# slit_lamp_goggles_PCB_compressed.net
KiCad netlist of a schematic drawn in Altium Designer
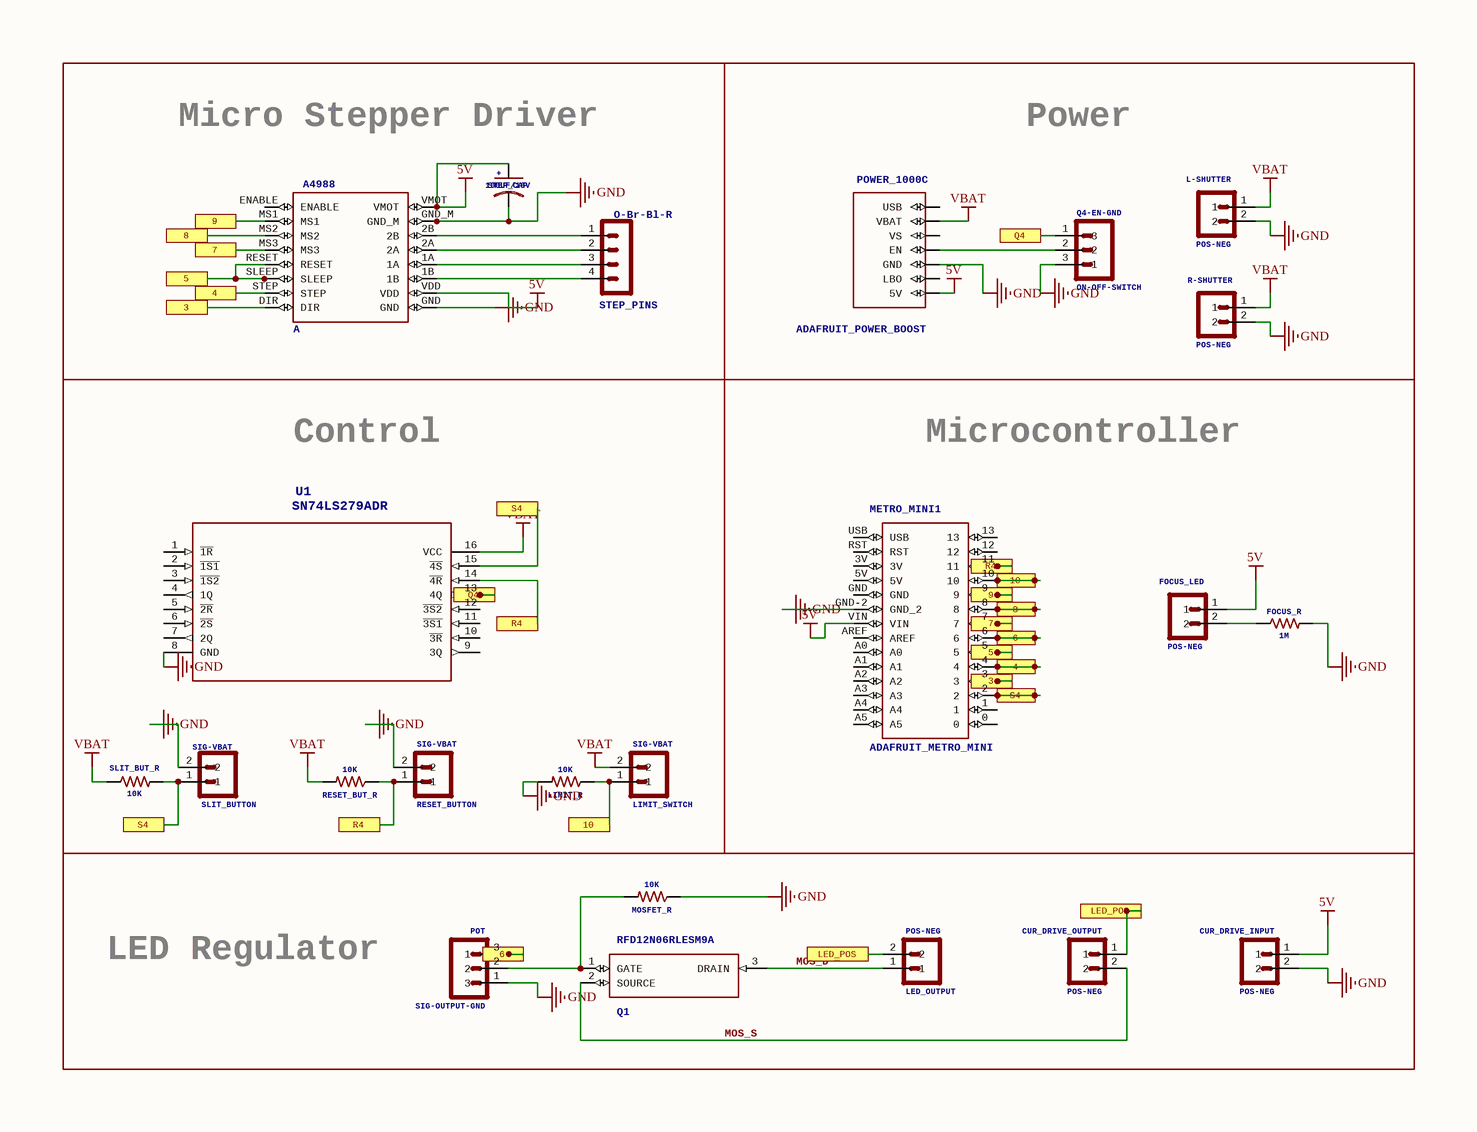
[diagram p0: slit_lamp_goggles_PCB_compressed.SchDoc]

(export (version "E")
  (design (tool "Eeschema 10.0.6"))
  (components
    (comp (ref "A4988")
      (value "A")
      (footprint "A4988")
      (description "Motor Drive for Stepper Motor")
      (libsource (lib "a4988_stepDriver") (part "A4988"))
    )
    (comp (ref "CUR_DRIVE_INPUT")
      (value "POS-NEG")
      (footprint "HDRVR2W64P254_1X2_558X254X850B")
      (description "2 Positions Header Connector 0.079\" (2.00mm) Through Hole Tin")
      (fields (field (name "MFR") "Sullins Connector Solutions") (field (name "MPN") "PPTC021LFBN-RC"))
      (libsource (lib "PiB_connectors") (part "1X02_PTH_VERT_FEMALE_2.54MM"))
    )
    (comp (ref "CUR_DRIVE_OUTPUT")
      (value "POS-NEG")
      (footprint "HDRVR2W64P254_1X2_558X254X850B")
      (description "2 Positions Header Connector 0.079\" (2.00mm) Through Hole Tin")
      (fields (field (name "MFR") "Sullins Connector Solutions") (field (name "MPN") "PPTC021LFBN-RC"))
      (libsource (lib "PiB_connectors") (part "1X02_PTH_VERT_FEMALE_2.54MM"))
    )
    (comp (ref "FOCUS_LED")
      (value "POS-NEG")
      (footprint "HDRVR2W64P254_1X2_558X254X850B")
      (description "2 Positions Header Connector 0.079\" (2.00mm) Through Hole Tin")
      (fields (field (name "MFR") "Sullins Connector Solutions") (field (name "MPN") "PPTC021LFBN-RC"))
      (libsource (lib "PiB_connectors") (part "1X02_PTH_VERT_FEMALE_2.54MM"))
    )
    (comp (ref "FOCUS_R")
      (value "1M")
      (footprint "RESISTOR-PTH-0207/7")
      (fields (field (name "CREATOR") "MrSwirlyEyes"))
      (libsource (lib "PiB_resistors") (part "RESISTOR_PTH-0207/7_1/8W-5%"))
    )
    (comp (ref "L-SHUTTER")
      (value "POS-NEG")
      (footprint "HDRVR2W64P254_1X2_558X254X850B")
      (description "2 Positions Header Connector 0.079\" (2.00mm) Through Hole Tin")
      (fields (field (name "MFR") "Sullins Connector Solutions") (field (name "MPN") "PPTC021LFBN-RC"))
      (libsource (lib "PiB_connectors") (part "1X02_PTH_VERT_FEMALE_2.54MM"))
    )
    (comp (ref "LED_OUTPUT")
      (value "POS-NEG")
      (footprint "HDRVR2W64P254_1X2_558X254X850B")
      (description "2 Positions Header Connector 0.079\" (2.00mm) Through Hole Tin")
      (fields (field (name "MFR") "Sullins Connector Solutions") (field (name "MPN") "PPTC021LFBN-RC"))
      (libsource (lib "PiB_connectors") (part "1X02_PTH_VERT_FEMALE_2.54MM"))
    )
    (comp (ref "LIMIT_R")
      (value "10K")
      (footprint "RESC1608X65_SMD-0603")
      (fields (field (name "MFR") "Yageo") (field (name "MPN") "RC0603JR-0710KL"))
      (libsource (lib "PiB_resistors") (part "10KΩ_SMD-0603_1/10W-5%"))
    )
    (comp (ref "LIMIT_SWITCH")
      (value "SIG-VBAT")
      (footprint "HDRVR2W64P254_1X2_558X254X850B")
      (description "2 Positions Header Connector 0.079\" (2.00mm) Through Hole Tin")
      (fields (field (name "MFR") "Sullins Connector Solutions") (field (name "MPN") "PPTC021LFBN-RC"))
      (libsource (lib "PiB_connectors") (part "1X02_PTH_VERT_FEMALE_2.54MM"))
    )
    (comp (ref "METRO_MINI1")
      (value "ADAFRUIT_METRO_MINI")
      (footprint "ADAFRUIT_METRO_MINI_2")
      (libsource (lib "adafruit_metro_mini") (part "ADAFRUIT_METRO_MINI"))
    )
    (comp (ref "MOSFET_R")
      (value "10K")
      (footprint "RESC1608X65_SMD-0603")
      (fields (field (name "MFR") "Yageo") (field (name "MPN") "RC0603JR-0710KL"))
      (libsource (lib "PiB_resistors") (part "10KΩ_SMD-0603_1/10W-5%"))
    )
    (comp (ref "ON-OFF-SWITCH")
      (value "Q4-EN-GND")
      (footprint "HDRVR3W64P254_1X3_812X254X850B")
      (fields (field (name "MFR") "Sullins Connector Solutions") (field (name "MPN") "PPTC031LFBN-RC"))
      (libsource (lib "PiB_connectors") (part "1X03_PTH_VERT_FEMALE_2.54MM"))
    )
    (comp (ref "POT")
      (value "SIG-OUTPUT-GND")
      (footprint "HDRVR3W64P254_1X3_812X254X850B")
      (fields (field (name "MFR") "Sullins Connector Solutions") (field (name "MPN") "PPTC031LFBN-RC"))
      (libsource (lib "PiB_connectors") (part "1X03_PTH_VERT_FEMALE_2.54MM"))
    )
    (comp (ref "POWER_1000C")
      (value "ADAFRUIT_POWER_BOOST")
      (footprint "ADAFRUIT_POWER_BOOST_1000C")
      (libsource (lib "adafruit_power_1000c") (part "ADAFRUIT_POWER_BOOST"))
    )
    (comp (ref "Q1")
      (value "RFD12N06RLESM9A")
      (footprint "DPAK3-CASE-369AS")
      (description "MOSFET   Source:  Datasheet")
      (fields
        (field (name "MOUSER_PART_NUMBER") "512-RFD12N06RLESM9A")
        (field (name "RS_PART_NUMBER") "8022143P")
      )
      (libsource (lib "mosfet_smd") (part "RFD12N06RLESM9A"))
    )
    (comp (ref "R-SHUTTER")
      (value "POS-NEG")
      (footprint "HDRVR2W64P254_1X2_558X254X850B")
      (description "2 Positions Header Connector 0.079\" (2.00mm) Through Hole Tin")
      (fields (field (name "MFR") "Sullins Connector Solutions") (field (name "MPN") "PPTC021LFBN-RC"))
      (libsource (lib "PiB_connectors") (part "1X02_PTH_VERT_FEMALE_2.54MM"))
    )
    (comp (ref "RESET_BUTTON")
      (value "SIG-VBAT")
      (footprint "HDRVR2W64P254_1X2_558X254X850B")
      (description "2 Positions Header Connector 0.079\" (2.00mm) Through Hole Tin")
      (fields (field (name "MFR") "Sullins Connector Solutions") (field (name "MPN") "PPTC021LFBN-RC"))
      (libsource (lib "PiB_connectors") (part "1X02_PTH_VERT_FEMALE_2.54MM"))
    )
    (comp (ref "RESET_BUT_R")
      (value "10K")
      (footprint "RESC1608X65_SMD-0603")
      (fields (field (name "MFR") "Yageo") (field (name "MPN") "RC0603JR-0710KL"))
      (libsource (lib "PiB_resistors") (part "10KΩ_SMD-0603_1/10W-5%"))
    )
    (comp (ref "SLIT_BUTTON")
      (value "SIG-VBAT")
      (footprint "HDRVR2W64P254_1X2_558X254X850B")
      (description "2 Positions Header Connector 0.079\" (2.00mm) Through Hole Tin")
      (fields (field (name "MFR") "Sullins Connector Solutions") (field (name "MPN") "PPTC021LFBN-RC"))
      (libsource (lib "PiB_connectors") (part "1X02_PTH_VERT_FEMALE_2.54MM"))
    )
    (comp (ref "SLIT_BUT_R")
      (value "10K")
      (footprint "RESC1608X65_SMD-0603")
      (fields (field (name "MFR") "Yageo") (field (name "MPN") "RC0603JR-0710KL"))
      (libsource (lib "PiB_resistors") (part "10KΩ_SMD-0603_1/10W-5%"))
    )
    (comp (ref "STEP_CAP")
      (value "100UF/16V")
      (footprint "_AE_SMD_L6.6-W6.6")
      (fields
        (field (name "+") "+")
        (field (name "MFR") "Panasonic Electronic Components")
        (field (name "MPN") "EEE-FK1C101P")
        (field (name "CREATOR") "MrSwirlyEyes")
      )
      (libsource (lib "PiB_capacitors") (part "100UF-POLARIZED_SMD_16V-20%_L6.6-W6.6"))
    )
    (comp (ref "STEP_PINS")
      (value "O-Br-Bl-R")
      (footprint "BM04B-SRSS-TB")
      (libsource (lib "con-JST SH") (part "BM04B-SRSS-TB"))
    )
    (comp (ref "U1")
      (value "SN74LS279ADR")
      (footprint "D16")
      (fields (field (name "MANUFACTURER") "Texas Instruments") (field (name "LIBRARYNAME") "SRlatch"))
      (libsource (lib "SRlatch") (part "SN74LS279ADR"))
    )
  )
  (nets
    (net (code "1") (name "/3") (class "Default")
      (node (ref "A4988") (pin "DIR") (pinfunction "DIR_DIR") (pintype "bidirectional"))
      (node (ref "METRO_MINI1") (pin "3") (pinfunction "3_3") (pintype "bidirectional"))
    )
    (net (code "2") (name "/4") (class "Default")
      (node (ref "A4988") (pin "STEP") (pinfunction "STEP_STEP") (pintype "bidirectional"))
      (node (ref "METRO_MINI1") (pin "4") (pinfunction "4_4") (pintype "bidirectional"))
    )
    (net (code "3") (name "/5") (class "Default")
      (node (ref "A4988") (pin "RESET") (pinfunction "RESET_RESET") (pintype "bidirectional"))
      (node (ref "A4988") (pin "SLEEP") (pinfunction "SLEEP_SLEEP") (pintype "bidirectional"))
      (node (ref "METRO_MINI1") (pin "5") (pinfunction "5_5") (pintype "bidirectional"))
    )
    (net (code "4") (name "/6") (class "Default")
      (node (ref "METRO_MINI1") (pin "6") (pinfunction "6_6") (pintype "bidirectional"))
      (node (ref "POT") (pin "3") (pinfunction "1_3") (pintype "passive"))
    )
    (net (code "5") (name "/7") (class "Default")
      (node (ref "A4988") (pin "MS3") (pinfunction "MS3_MS3") (pintype "bidirectional"))
      (node (ref "METRO_MINI1") (pin "7") (pinfunction "7_7") (pintype "bidirectional"))
    )
    (net (code "6") (name "/8") (class "Default")
      (node (ref "A4988") (pin "MS2") (pinfunction "MS2_MS2") (pintype "bidirectional"))
      (node (ref "METRO_MINI1") (pin "8") (pinfunction "8_8") (pintype "bidirectional"))
    )
    (net (code "7") (name "/9") (class "Default")
      (node (ref "A4988") (pin "MS1") (pinfunction "MS1_MS1") (pintype "bidirectional"))
      (node (ref "METRO_MINI1") (pin "9") (pinfunction "9_9") (pintype "bidirectional"))
    )
    (net (code "8") (name "/10") (class "Default")
      (node (ref "LIMIT_R") (pin "1") (pinfunction "1_1") (pintype "passive"))
      (node (ref "LIMIT_SWITCH") (pin "1") (pinfunction "1_1") (pintype "passive"))
      (node (ref "METRO_MINI1") (pin "10") (pinfunction "10_10") (pintype "bidirectional"))
    )
    (net (code "9") (name "/LED_POS") (class "Default")
      (node (ref "CUR_DRIVE_OUTPUT") (pin "1") (pinfunction "1_1") (pintype "passive"))
      (node (ref "LED_OUTPUT") (pin "2") (pinfunction "2_2") (pintype "passive"))
    )
    (net (code "10") (name "/MOS_D") (class "Default")
      (node (ref "LED_OUTPUT") (pin "1") (pinfunction "1_1") (pintype "passive"))
      (node (ref "Q1") (pin "3") (pinfunction "DRAIN_3") (pintype "input"))
    )
    (net (code "11") (name "/MOS_S") (class "Default")
      (node (ref "CUR_DRIVE_OUTPUT") (pin "2") (pinfunction "2_2") (pintype "passive"))
      (node (ref "Q1") (pin "2") (pinfunction "SOURCE_2") (pintype "bidirectional"))
    )
    (net (code "12") (name "/Q4") (class "Default")
      (node (ref "ON-OFF-SWITCH") (pin "1") (pinfunction "3_1") (pintype "passive"))
      (node (ref "U1") (pin "13") (pinfunction "4Q_13") (pintype "output"))
    )
    (net (code "13") (name "/R4") (class "Default")
      (node (ref "METRO_MINI1") (pin "11") (pinfunction "11_11") (pintype "bidirectional"))
      (node (ref "RESET_BUTTON") (pin "1") (pinfunction "1_1") (pintype "passive"))
      (node (ref "RESET_BUT_R") (pin "1") (pinfunction "1_1") (pintype "passive"))
      (node (ref "U1") (pin "14") (pinfunction "~{4R}_14") (pintype "input"))
    )
    (net (code "14") (name "/S4") (class "Default")
      (node (ref "METRO_MINI1") (pin "2") (pinfunction "2_2") (pintype "bidirectional"))
      (node (ref "SLIT_BUTTON") (pin "1") (pinfunction "1_1") (pintype "passive"))
      (node (ref "SLIT_BUT_R") (pin "2") (pinfunction "2_2") (pintype "passive"))
      (node (ref "U1") (pin "15") (pinfunction "~{4S}_15") (pintype "input"))
    )
    (net (code "15") (name "5V") (class "Default")
      (node (ref "A4988") (pin "VDD") (pinfunction "VDD_VDD") (pintype "bidirectional"))
      (node (ref "A4988") (pin "VMOT") (pinfunction "VMOT_VMOT") (pintype "bidirectional"))
      (node (ref "CUR_DRIVE_INPUT") (pin "1") (pinfunction "1_1") (pintype "passive"))
      (node (ref "FOCUS_LED") (pin "1") (pinfunction "1_1") (pintype "passive"))
      (node (ref "METRO_MINI1") (pin "VIN") (pinfunction "VIN_VIN") (pintype "bidirectional"))
      (node (ref "POWER_1000C") (pin "5V") (pinfunction "5V_5V") (pintype "bidirectional"))
      (node (ref "STEP_CAP") (pin "A") (pinfunction "A_A") (pintype "passive"))
    )
    (net (code "16") (name "GND") (class "Default")
      (node (ref "A4988") (pin "GND") (pinfunction "GND_GND") (pintype "bidirectional"))
      (node (ref "A4988") (pin "GND_M") (pinfunction "GND_M_GND_M") (pintype "bidirectional"))
      (node (ref "CUR_DRIVE_INPUT") (pin "2") (pinfunction "2_2") (pintype "passive"))
      (node (ref "FOCUS_R") (pin "2") (pinfunction "2_2") (pintype "passive"))
      (node (ref "L-SHUTTER") (pin "2") (pinfunction "2_2") (pintype "passive"))
      (node (ref "LIMIT_R") (pin "2") (pinfunction "2_2") (pintype "passive"))
      (node (ref "METRO_MINI1") (pin "GND-2") (pinfunction "GND_2_GND-2") (pintype "bidirectional"))
      (node (ref "MOSFET_R") (pin "1") (pinfunction "1_1") (pintype "passive"))
      (node (ref "ON-OFF-SWITCH") (pin "3") (pinfunction "1_3") (pintype "passive"))
      (node (ref "POT") (pin "1") (pinfunction "3_1") (pintype "passive"))
      (node (ref "POWER_1000C") (pin "GND@0_GND@1") (pinfunction "GND_GND@0_GND@1") (pintype "bidirectional"))
      (node (ref "R-SHUTTER") (pin "2") (pinfunction "2_2") (pintype "passive"))
      (node (ref "RESET_BUTTON") (pin "2") (pinfunction "2_2") (pintype "passive"))
      (node (ref "SLIT_BUTTON") (pin "2") (pinfunction "2_2") (pintype "passive"))
      (node (ref "STEP_CAP") (pin "K") (pinfunction "K_K") (pintype "passive"))
      (node (ref "U1") (pin "8") (pinfunction "GND_8") (pintype "power_in"))
    )
    (net (code "17") (name "Net-(A4988-Pad1A)") (class "Default")
      (node (ref "A4988") (pin "1A") (pinfunction "1A_1A") (pintype "bidirectional"))
      (node (ref "STEP_PINS") (pin "3") (pinfunction "3_3") (pintype "passive"))
    )
    (net (code "18") (name "Net-(A4988-Pad1B)") (class "Default")
      (node (ref "A4988") (pin "1B") (pinfunction "1B_1B") (pintype "bidirectional"))
      (node (ref "STEP_PINS") (pin "4") (pinfunction "4_4") (pintype "passive"))
    )
    (net (code "19") (name "Net-(A4988-Pad2A)") (class "Default")
      (node (ref "A4988") (pin "2A") (pinfunction "2A_2A") (pintype "bidirectional"))
      (node (ref "STEP_PINS") (pin "2") (pinfunction "2_2") (pintype "passive"))
    )
    (net (code "20") (name "Net-(A4988-Pad2B)") (class "Default")
      (node (ref "A4988") (pin "2B") (pinfunction "2B_2B") (pintype "bidirectional"))
      (node (ref "STEP_PINS") (pin "1") (pinfunction "1_1") (pintype "passive"))
    )
    (net (code "21") (name "Net-(FOCUS_LED-Pad2)") (class "Default")
      (node (ref "FOCUS_LED") (pin "2") (pinfunction "2_2") (pintype "passive"))
      (node (ref "FOCUS_R") (pin "1") (pinfunction "1_1") (pintype "passive"))
    )
    (net (code "22") (name "Net-(ON-OFF-SWITCH-Pad2)") (class "Default")
      (node (ref "ON-OFF-SWITCH") (pin "2") (pinfunction "2_2") (pintype "passive"))
      (node (ref "POWER_1000C") (pin "EN") (pinfunction "EN_EN") (pintype "bidirectional"))
    )
    (net (code "23") (name "Net-(Q1-GATE)") (class "Default")
      (node (ref "MOSFET_R") (pin "2") (pinfunction "2_2") (pintype "passive"))
      (node (ref "POT") (pin "2") (pinfunction "2_2") (pintype "passive"))
      (node (ref "Q1") (pin "1") (pinfunction "GATE_1") (pintype "bidirectional"))
    )
    (net (code "24") (name "VBAT") (class "Default")
      (node (ref "L-SHUTTER") (pin "1") (pinfunction "1_1") (pintype "passive"))
      (node (ref "LIMIT_SWITCH") (pin "2") (pinfunction "2_2") (pintype "passive"))
      (node (ref "POWER_1000C") (pin "BAT") (pinfunction "VBAT_BAT") (pintype "bidirectional"))
      (node (ref "R-SHUTTER") (pin "1") (pinfunction "1_1") (pintype "passive"))
      (node (ref "RESET_BUT_R") (pin "2") (pinfunction "2_2") (pintype "passive"))
      (node (ref "SLIT_BUT_R") (pin "1") (pinfunction "1_1") (pintype "passive"))
      (node (ref "U1") (pin "16") (pinfunction "VCC_16") (pintype "power_in"))
    )
    (net (code "25") (name "unconnected-(A4988-PadENABLE)") (class "Default")
      (node (ref "A4988") (pin "ENABLE") (pinfunction "ENABLE_ENABLE") (pintype "bidirectional"))
    )
    (net (code "26") (name "unconnected-(METRO_MINI1-Pad0)") (class "Default")
      (node (ref "METRO_MINI1") (pin "0") (pinfunction "0_0") (pintype "bidirectional"))
    )
    (net (code "27") (name "unconnected-(METRO_MINI1-Pad1)") (class "Default")
      (node (ref "METRO_MINI1") (pin "1") (pinfunction "1_1") (pintype "bidirectional"))
    )
    (net (code "28") (name "unconnected-(METRO_MINI1-Pad3V)") (class "Default")
      (node (ref "METRO_MINI1") (pin "3V") (pinfunction "3V_3V") (pintype "bidirectional"))
    )
    (net (code "29") (name "unconnected-(METRO_MINI1-Pad5V)") (class "Default")
      (node (ref "METRO_MINI1") (pin "5V") (pinfunction "5V_5V") (pintype "bidirectional"))
    )
    (net (code "30") (name "unconnected-(METRO_MINI1-Pad12)") (class "Default")
      (node (ref "METRO_MINI1") (pin "12") (pinfunction "12_12") (pintype "bidirectional"))
    )
    (net (code "31") (name "unconnected-(METRO_MINI1-Pad13)") (class "Default")
      (node (ref "METRO_MINI1") (pin "13") (pinfunction "13_13") (pintype "bidirectional"))
    )
    (net (code "32") (name "unconnected-(METRO_MINI1-PadA0)") (class "Default")
      (node (ref "METRO_MINI1") (pin "A0") (pinfunction "A0_A0") (pintype "bidirectional"))
    )
    (net (code "33") (name "unconnected-(METRO_MINI1-PadA1)") (class "Default")
      (node (ref "METRO_MINI1") (pin "A1") (pinfunction "A1_A1") (pintype "bidirectional"))
    )
    (net (code "34") (name "unconnected-(METRO_MINI1-PadA2)") (class "Default")
      (node (ref "METRO_MINI1") (pin "A2") (pinfunction "A2_A2") (pintype "bidirectional"))
    )
    (net (code "35") (name "unconnected-(METRO_MINI1-PadA3)") (class "Default")
      (node (ref "METRO_MINI1") (pin "A3") (pinfunction "A3_A3") (pintype "bidirectional"))
    )
    (net (code "36") (name "unconnected-(METRO_MINI1-PadA4)") (class "Default")
      (node (ref "METRO_MINI1") (pin "A4") (pinfunction "A4_A4") (pintype "bidirectional"))
    )
    (net (code "37") (name "unconnected-(METRO_MINI1-PadA5)") (class "Default")
      (node (ref "METRO_MINI1") (pin "A5") (pinfunction "A5_A5") (pintype "bidirectional"))
    )
    (net (code "38") (name "unconnected-(METRO_MINI1-PadAREF)") (class "Default")
      (node (ref "METRO_MINI1") (pin "AREF") (pinfunction "AREF_AREF") (pintype "bidirectional"))
    )
    (net (code "39") (name "unconnected-(METRO_MINI1-PadGND)") (class "Default")
      (node (ref "METRO_MINI1") (pin "GND") (pinfunction "GND_GND") (pintype "bidirectional"))
    )
    (net (code "40") (name "unconnected-(METRO_MINI1-PadRST)") (class "Default")
      (node (ref "METRO_MINI1") (pin "RST") (pinfunction "RST_RST") (pintype "bidirectional"))
    )
    (net (code "41") (name "unconnected-(METRO_MINI1-PadUSB)") (class "Default")
      (node (ref "METRO_MINI1") (pin "USB") (pinfunction "USB_USB") (pintype "bidirectional"))
    )
    (net (code "42") (name "unconnected-(POWER_1000C-LBO-PadLB0)") (class "Default")
      (node (ref "POWER_1000C") (pin "LB0") (pinfunction "LBO_LB0") (pintype "bidirectional"))
    )
    (net (code "43") (name "unconnected-(POWER_1000C-PadUSB)") (class "Default")
      (node (ref "POWER_1000C") (pin "USB") (pinfunction "USB_USB") (pintype "bidirectional"))
    )
    (net (code "44") (name "unconnected-(POWER_1000C-PadVS)") (class "Default")
      (node (ref "POWER_1000C") (pin "VS") (pinfunction "VS_VS") (pintype "bidirectional"))
    )
    (net (code "45") (name "unconnected-(U1-1Q-Pad4)") (class "Default")
      (node (ref "U1") (pin "4") (pinfunction "1Q_4") (pintype "output"))
    )
    (net (code "46") (name "unconnected-(U1-2Q-Pad7)") (class "Default")
      (node (ref "U1") (pin "7") (pinfunction "2Q_7") (pintype "output"))
    )
    (net (code "47") (name "unconnected-(U1-3Q-Pad9)") (class "Default")
      (node (ref "U1") (pin "9") (pinfunction "3Q_9") (pintype "output"))
    )
    (net (code "48") (name "unconnected-(U1-~{1R}-Pad1)") (class "Default")
      (node (ref "U1") (pin "1") (pinfunction "~{1R}_1") (pintype "input"))
    )
    (net (code "49") (name "unconnected-(U1-~{1S1}-Pad2)") (class "Default")
      (node (ref "U1") (pin "2") (pinfunction "~{1S1}_2") (pintype "input"))
    )
    (net (code "50") (name "unconnected-(U1-~{1S2}-Pad3)") (class "Default")
      (node (ref "U1") (pin "3") (pinfunction "~{1S2}_3") (pintype "input"))
    )
    (net (code "51") (name "unconnected-(U1-~{2R}-Pad5)") (class "Default")
      (node (ref "U1") (pin "5") (pinfunction "~{2R}_5") (pintype "input"))
    )
    (net (code "52") (name "unconnected-(U1-~{2S}-Pad6)") (class "Default")
      (node (ref "U1") (pin "6") (pinfunction "~{2S}_6") (pintype "input"))
    )
    (net (code "53") (name "unconnected-(U1-~{3R}-Pad10)") (class "Default")
      (node (ref "U1") (pin "10") (pinfunction "~{3R}_10") (pintype "input"))
    )
    (net (code "54") (name "unconnected-(U1-~{3S1}-Pad11)") (class "Default")
      (node (ref "U1") (pin "11") (pinfunction "~{3S1}_11") (pintype "input"))
    )
    (net (code "55") (name "unconnected-(U1-~{3S2}-Pad12)") (class "Default")
      (node (ref "U1") (pin "12") (pinfunction "~{3S2}_12") (pintype "input"))
    )
  )
)
